# p128control.net
KiCad netlist of a schematic drawn in EAGLE
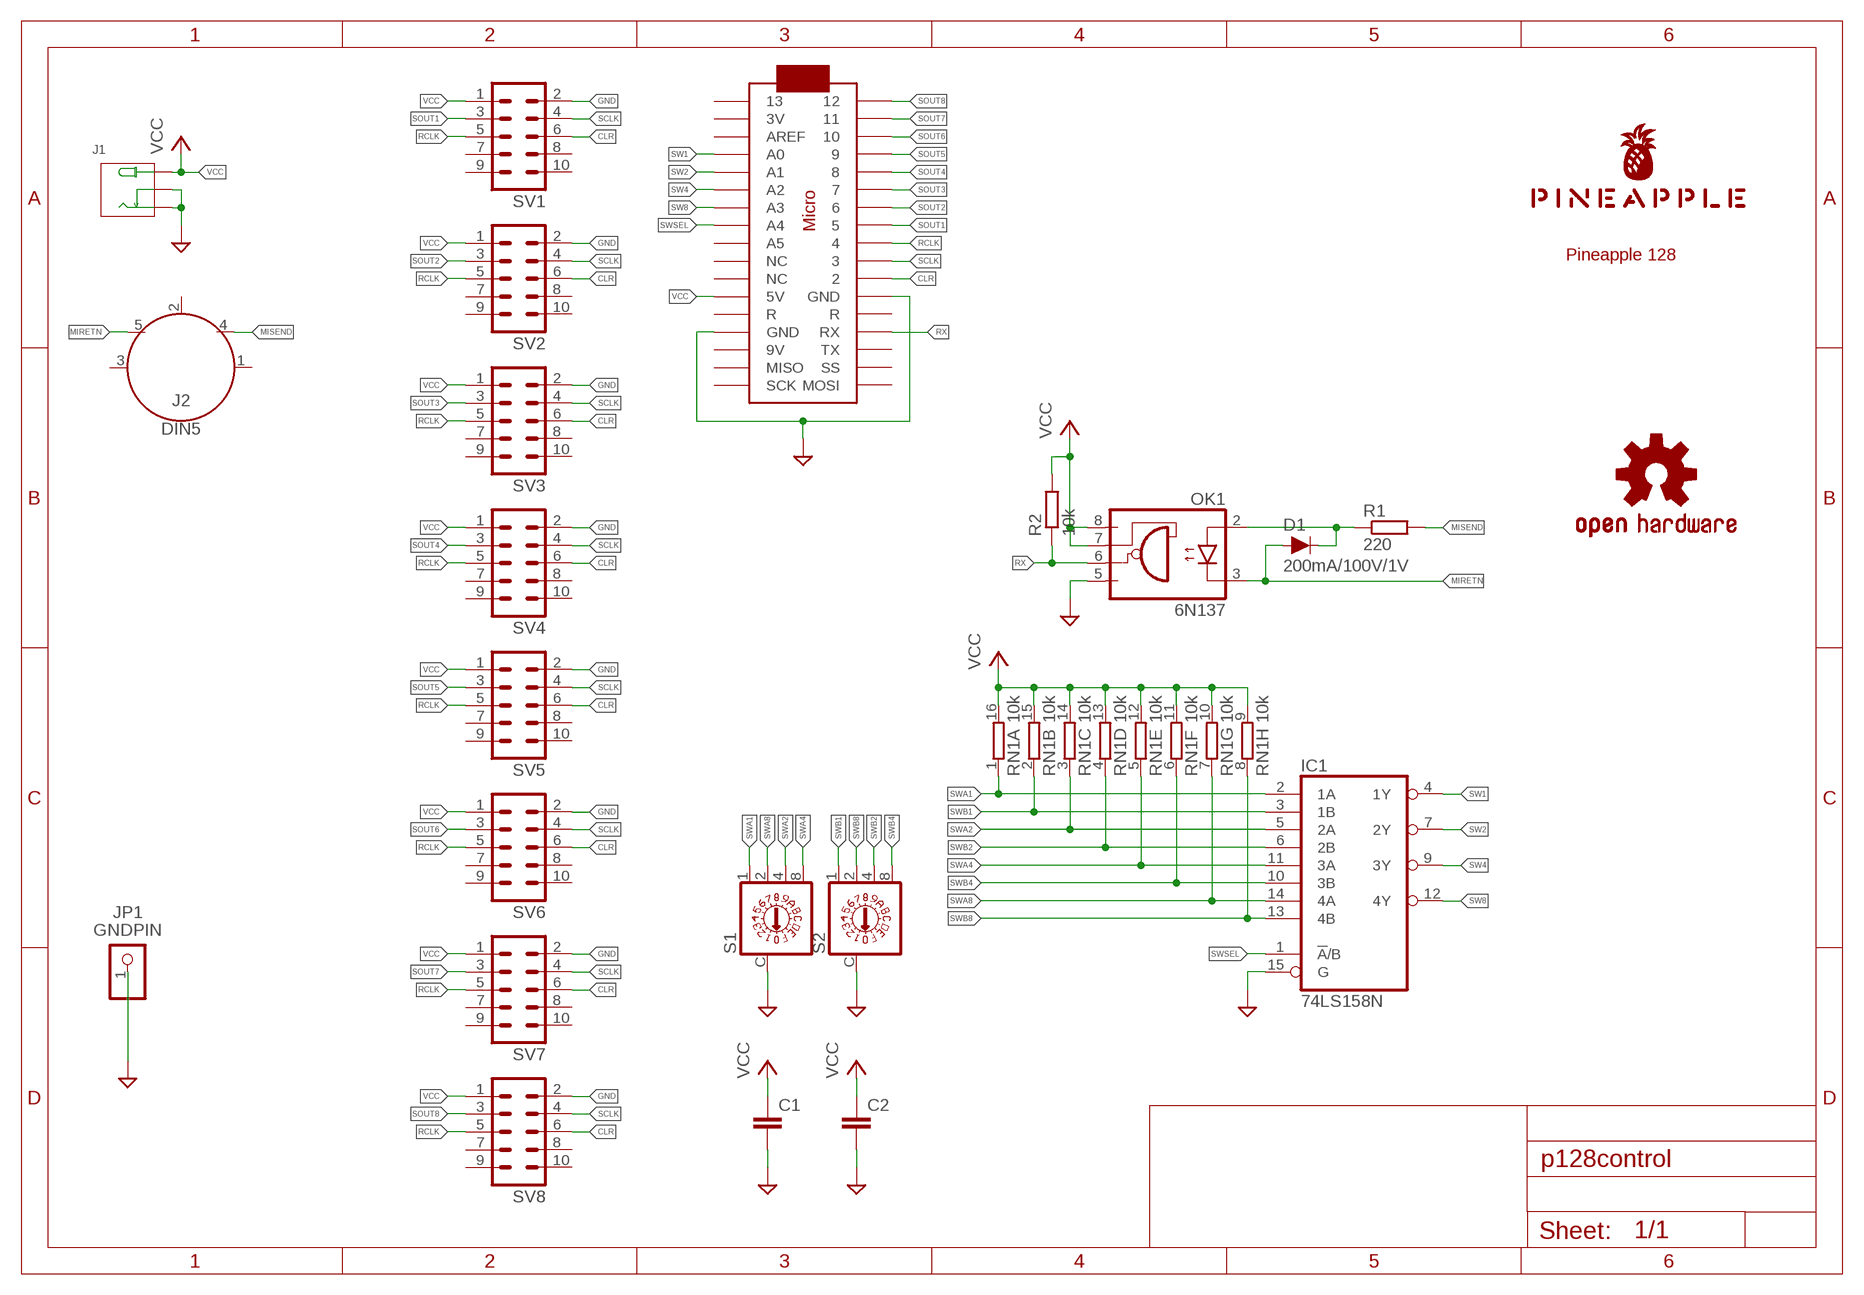
[diagram p0: schematic, sheet 1]

(export (version "E")
  (design (tool "Eeschema 10.0.6"))
  (components
    (comp (ref "C1")
      (value "C-EU025-024X044")
      (footprint "eagle-import:C025-024X044")
      (libsource (lib "eagle-import") (part "C-EU025-024X044"))
    )
    (comp (ref "C2")
      (value "C-EU025-024X044")
      (footprint "eagle-import:C025-024X044")
      (libsource (lib "eagle-import") (part "C-EU025-024X044"))
    )
    (comp (ref "D1")
      (value "200mA/100V/1V")
      (footprint "eagle-import:DIODE-1N4148")
      (libsource (lib "eagle-import") (part "DIODE-1N4148"))
    )
    (comp (ref "IC1")
      (value "74LS158N")
      (footprint "eagle-import:DIL16")
      (libsource (lib "eagle-import") (part "74158NLS"))
    )
    (comp (ref "J1")
      (value "JACK-DC-005'DC-005'")
      (footprint "eagle-import:3P-L14.2_W11.0_H9.0MM")
      (libsource (lib "eagle-import") (part "JACK-DC-005'DC-005'"))
    )
    (comp (ref "J2")
      (value "DIN5")
      (footprint "eagle-import:DIN5-RA-PTH")
      (libsource (lib "eagle-import") (part "DIN5"))
    )
    (comp (ref "JP1")
      (value "GNDPIN")
      (footprint "eagle-import:1X01")
      (libsource (lib "eagle-import") (part "PINHD-1X1"))
    )
    (comp (ref "LOGO1")
      (value "OSHW-LOGOS-COPPER")
      (footprint "eagle-import:OSHW-LOGO-S_COPPER")
      (libsource (lib "eagle-import") (part "OSHW-LOGOS-COPPER"))
    )
    (comp (ref "OK1")
      (value "6N137")
      (footprint "eagle-import:DIL08")
      (libsource (lib "eagle-import") (part "6N137"))
    )
    (comp (ref "R1")
      (value "220")
      (footprint "eagle-import:0204_5")
      (libsource (lib "eagle-import") (part "R-EU_0204/5"))
    )
    (comp (ref "R2")
      (value "10k")
      (footprint "eagle-import:0204_5")
      (libsource (lib "eagle-import") (part "R-EU_0204/5"))
    )
    (comp (ref "RN1")
      (value "10k")
      (footprint "eagle-import:DIL16")
      (libsource (lib "eagle-import") (part "8R-N"))
    )
    (comp (ref "S1")
      (value "A1353HEX")
      (footprint "eagle-import:A1353HEX")
      (libsource (lib "eagle-import") (part "A1353HEX"))
    )
    (comp (ref "S2")
      (value "A1353HEX")
      (footprint "eagle-import:A1353HEX")
      (libsource (lib "eagle-import") (part "A1353HEX"))
    )
    (comp (ref "SV1")
      (value "ML10")
      (footprint "eagle-import:ML10")
      (libsource (lib "eagle-import") (part "ML10"))
    )
    (comp (ref "SV2")
      (value "ML10")
      (footprint "eagle-import:ML10")
      (libsource (lib "eagle-import") (part "ML10"))
    )
    (comp (ref "SV3")
      (value "ML10")
      (footprint "eagle-import:ML10")
      (libsource (lib "eagle-import") (part "ML10"))
    )
    (comp (ref "SV4")
      (value "ML10")
      (footprint "eagle-import:ML10")
      (libsource (lib "eagle-import") (part "ML10"))
    )
    (comp (ref "SV5")
      (value "ML10")
      (footprint "eagle-import:ML10")
      (libsource (lib "eagle-import") (part "ML10"))
    )
    (comp (ref "SV6")
      (value "ML10")
      (footprint "eagle-import:ML10")
      (libsource (lib "eagle-import") (part "ML10"))
    )
    (comp (ref "SV7")
      (value "ML10")
      (footprint "eagle-import:ML10")
      (libsource (lib "eagle-import") (part "ML10"))
    )
    (comp (ref "SV8")
      (value "ML10")
      (footprint "eagle-import:ML10")
      (libsource (lib "eagle-import") (part "ML10"))
    )
    (comp (ref "U$1")
      (value "PINEAPPLE450_SILK")
      (footprint "eagle-import:PINEAPPLE450_SILK")
      (libsource (lib "eagle-import") (part "PINEAPPLE450_SILK"))
    )
    (comp (ref "U$2")
      (value "ARDUINOMICRO")
      (footprint "eagle-import:ARDUINOMICRO")
      (libsource (lib "eagle-import") (part "ARDUINOMICRO"))
    )
  )
  (nets
    (net (code "1") (name "CLR") (class "Default")
      (node (ref "SV1") (pin "6") (pinfunction "6_6") (pintype "passive"))
      (node (ref "SV2") (pin "6") (pinfunction "6_6") (pintype "passive"))
      (node (ref "SV3") (pin "6") (pinfunction "6_6") (pintype "passive"))
      (node (ref "SV4") (pin "6") (pinfunction "6_6") (pintype "passive"))
      (node (ref "SV5") (pin "6") (pinfunction "6_6") (pintype "passive"))
      (node (ref "SV6") (pin "6") (pinfunction "6_6") (pintype "passive"))
      (node (ref "SV7") (pin "6") (pinfunction "6_6") (pintype "passive"))
      (node (ref "SV8") (pin "6") (pinfunction "6_6") (pintype "passive"))
      (node (ref "U$2") (pin "P$11") (pinfunction "2_P$11") (pintype "bidirectional"))
    )
    (net (code "2") (name "GND") (class "Default")
      (node (ref "C1") (pin "2") (pinfunction "2_2") (pintype "passive"))
      (node (ref "C2") (pin "2") (pinfunction "2_2") (pintype "passive"))
      (node (ref "IC1") (pin "15") (pinfunction "G_15") (pintype "input"))
      (node (ref "J1") (pin "-1") (pinfunction "-_-1") (pintype "bidirectional"))
      (node (ref "J1") (pin "-2") (pinfunction "CDN_-2") (pintype "bidirectional"))
      (node (ref "JP1") (pin "1") (pinfunction "1_1") (pintype "passive"))
      (node (ref "OK1") (pin "5") (pinfunction "GND_5") (pintype "passive"))
      (node (ref "S1") (pin "C") (pinfunction "C_C") (pintype "passive"))
      (node (ref "S2") (pin "C") (pinfunction "C_C") (pintype "passive"))
      (node (ref "SV1") (pin "2") (pinfunction "2_2") (pintype "passive"))
      (node (ref "SV2") (pin "2") (pinfunction "2_2") (pintype "passive"))
      (node (ref "SV3") (pin "2") (pinfunction "2_2") (pintype "passive"))
      (node (ref "SV4") (pin "2") (pinfunction "2_2") (pintype "passive"))
      (node (ref "SV5") (pin "2") (pinfunction "2_2") (pintype "passive"))
      (node (ref "SV6") (pin "2") (pinfunction "2_2") (pintype "passive"))
      (node (ref "SV7") (pin "2") (pinfunction "2_2") (pintype "passive"))
      (node (ref "SV8") (pin "2") (pinfunction "2_2") (pintype "passive"))
      (node (ref "U$2") (pin "P$12") (pinfunction "GND_P$12") (pintype "bidirectional"))
      (node (ref "U$2") (pin "P$21") (pinfunction "GND_P$21") (pintype "bidirectional"))
    )
    (net (code "3") (name "MIRETN") (class "Default")
      (node (ref "D1") (pin "A") (pinfunction "A_A") (pintype "passive"))
      (node (ref "J2") (pin "5") (pinfunction "5_5") (pintype "bidirectional"))
      (node (ref "OK1") (pin "3") (pinfunction "C_3") (pintype "passive"))
    )
    (net (code "4") (name "MISEND") (class "Default")
      (node (ref "J2") (pin "4") (pinfunction "4_4") (pintype "bidirectional"))
      (node (ref "R1") (pin "2") (pinfunction "2_2") (pintype "passive"))
    )
    (net (code "5") (name "Net-(OK1-A)") (class "Default")
      (node (ref "D1") (pin "C") (pinfunction "C_C") (pintype "passive"))
      (node (ref "OK1") (pin "2") (pinfunction "A_2") (pintype "passive"))
      (node (ref "R1") (pin "1") (pinfunction "1_1") (pintype "passive"))
    )
    (net (code "6") (name "RCLK") (class "Default")
      (node (ref "SV1") (pin "5") (pinfunction "5_5") (pintype "passive"))
      (node (ref "SV2") (pin "5") (pinfunction "5_5") (pintype "passive"))
      (node (ref "SV3") (pin "5") (pinfunction "5_5") (pintype "passive"))
      (node (ref "SV4") (pin "5") (pinfunction "5_5") (pintype "passive"))
      (node (ref "SV5") (pin "5") (pinfunction "5_5") (pintype "passive"))
      (node (ref "SV6") (pin "5") (pinfunction "5_5") (pintype "passive"))
      (node (ref "SV7") (pin "5") (pinfunction "5_5") (pintype "passive"))
      (node (ref "SV8") (pin "5") (pinfunction "5_5") (pintype "passive"))
      (node (ref "U$2") (pin "P$9") (pinfunction "4_P$9") (pintype "bidirectional"))
    )
    (net (code "7") (name "RX") (class "Default")
      (node (ref "OK1") (pin "6") (pinfunction "VO_6") (pintype "passive"))
      (node (ref "R2") (pin "1") (pinfunction "1_1") (pintype "passive"))
      (node (ref "U$2") (pin "P$14") (pinfunction "RX_P$14") (pintype "bidirectional"))
    )
    (net (code "8") (name "SCLK") (class "Default")
      (node (ref "SV1") (pin "4") (pinfunction "4_4") (pintype "passive"))
      (node (ref "SV2") (pin "4") (pinfunction "4_4") (pintype "passive"))
      (node (ref "SV3") (pin "4") (pinfunction "4_4") (pintype "passive"))
      (node (ref "SV4") (pin "4") (pinfunction "4_4") (pintype "passive"))
      (node (ref "SV5") (pin "4") (pinfunction "4_4") (pintype "passive"))
      (node (ref "SV6") (pin "4") (pinfunction "4_4") (pintype "passive"))
      (node (ref "SV7") (pin "4") (pinfunction "4_4") (pintype "passive"))
      (node (ref "SV8") (pin "4") (pinfunction "4_4") (pintype "passive"))
      (node (ref "U$2") (pin "P$10") (pinfunction "3_P$10") (pintype "bidirectional"))
    )
    (net (code "9") (name "SOUT1") (class "Default")
      (node (ref "SV1") (pin "3") (pinfunction "3_3") (pintype "passive"))
      (node (ref "U$2") (pin "P$8") (pinfunction "5_P$8") (pintype "bidirectional"))
    )
    (net (code "10") (name "SOUT2") (class "Default")
      (node (ref "SV2") (pin "3") (pinfunction "3_3") (pintype "passive"))
      (node (ref "U$2") (pin "P$7") (pinfunction "6_P$7") (pintype "bidirectional"))
    )
    (net (code "11") (name "SOUT3") (class "Default")
      (node (ref "SV3") (pin "3") (pinfunction "3_3") (pintype "passive"))
      (node (ref "U$2") (pin "P$6") (pinfunction "7_P$6") (pintype "bidirectional"))
    )
    (net (code "12") (name "SOUT4") (class "Default")
      (node (ref "SV4") (pin "3") (pinfunction "3_3") (pintype "passive"))
      (node (ref "U$2") (pin "P$5") (pinfunction "8_P$5") (pintype "bidirectional"))
    )
    (net (code "13") (name "SOUT5") (class "Default")
      (node (ref "SV5") (pin "3") (pinfunction "3_3") (pintype "passive"))
      (node (ref "U$2") (pin "P$4") (pinfunction "9_P$4") (pintype "bidirectional"))
    )
    (net (code "14") (name "SOUT6") (class "Default")
      (node (ref "SV6") (pin "3") (pinfunction "3_3") (pintype "passive"))
      (node (ref "U$2") (pin "P$3") (pinfunction "10_P$3") (pintype "bidirectional"))
    )
    (net (code "15") (name "SOUT7") (class "Default")
      (node (ref "SV7") (pin "3") (pinfunction "3_3") (pintype "passive"))
      (node (ref "U$2") (pin "P$2") (pinfunction "11_P$2") (pintype "bidirectional"))
    )
    (net (code "16") (name "SOUT8") (class "Default")
      (node (ref "SV8") (pin "3") (pinfunction "3_3") (pintype "passive"))
      (node (ref "U$2") (pin "P$1") (pinfunction "12_P$1") (pintype "bidirectional"))
    )
    (net (code "17") (name "SW1") (class "Default")
      (node (ref "IC1") (pin "4") (pinfunction "1Y_4") (pintype "output"))
      (node (ref "U$2") (pin "P$31") (pinfunction "A0_P$31") (pintype "bidirectional"))
    )
    (net (code "18") (name "SW2") (class "Default")
      (node (ref "IC1") (pin "7") (pinfunction "2Y_7") (pintype "output"))
      (node (ref "U$2") (pin "P$30") (pinfunction "A1_P$30") (pintype "bidirectional"))
    )
    (net (code "19") (name "SW4") (class "Default")
      (node (ref "IC1") (pin "9") (pinfunction "3Y_9") (pintype "output"))
      (node (ref "U$2") (pin "P$29") (pinfunction "A2_P$29") (pintype "bidirectional"))
    )
    (net (code "20") (name "SW8") (class "Default")
      (node (ref "IC1") (pin "12") (pinfunction "4Y_12") (pintype "output"))
      (node (ref "U$2") (pin "P$28") (pinfunction "A3_P$28") (pintype "bidirectional"))
    )
    (net (code "21") (name "SWA1") (class "Default")
      (node (ref "IC1") (pin "2") (pinfunction "1A_2") (pintype "input"))
      (node (ref "RN1") (pin "1") (pinfunction "1_1") (pintype "passive"))
      (node (ref "S1") (pin "1") (pinfunction "1_1") (pintype "passive"))
    )
    (net (code "22") (name "SWA2") (class "Default")
      (node (ref "IC1") (pin "5") (pinfunction "2A_5") (pintype "input"))
      (node (ref "RN1") (pin "3") (pinfunction "1_3") (pintype "passive"))
      (node (ref "S1") (pin "4") (pinfunction "4_4") (pintype "passive"))
    )
    (net (code "23") (name "SWA4") (class "Default")
      (node (ref "IC1") (pin "11") (pinfunction "3A_11") (pintype "input"))
      (node (ref "RN1") (pin "5") (pinfunction "1_5") (pintype "passive"))
      (node (ref "S1") (pin "8") (pinfunction "8_8") (pintype "passive"))
    )
    (net (code "24") (name "SWA8") (class "Default")
      (node (ref "IC1") (pin "14") (pinfunction "4A_14") (pintype "input"))
      (node (ref "RN1") (pin "7") (pinfunction "1_7") (pintype "passive"))
      (node (ref "S1") (pin "2") (pinfunction "2_2") (pintype "passive"))
    )
    (net (code "25") (name "SWB1") (class "Default")
      (node (ref "IC1") (pin "3") (pinfunction "1B_3") (pintype "input"))
      (node (ref "RN1") (pin "2") (pinfunction "1_2") (pintype "passive"))
      (node (ref "S2") (pin "1") (pinfunction "1_1") (pintype "passive"))
    )
    (net (code "26") (name "SWB2") (class "Default")
      (node (ref "IC1") (pin "6") (pinfunction "2B_6") (pintype "input"))
      (node (ref "RN1") (pin "4") (pinfunction "1_4") (pintype "passive"))
      (node (ref "S2") (pin "4") (pinfunction "4_4") (pintype "passive"))
    )
    (net (code "27") (name "SWB4") (class "Default")
      (node (ref "IC1") (pin "10") (pinfunction "3B_10") (pintype "input"))
      (node (ref "RN1") (pin "6") (pinfunction "1_6") (pintype "passive"))
      (node (ref "S2") (pin "8") (pinfunction "8_8") (pintype "passive"))
    )
    (net (code "28") (name "SWB8") (class "Default")
      (node (ref "IC1") (pin "13") (pinfunction "4B_13") (pintype "input"))
      (node (ref "RN1") (pin "8") (pinfunction "1_8") (pintype "passive"))
      (node (ref "S2") (pin "2") (pinfunction "2_2") (pintype "passive"))
    )
    (net (code "29") (name "SWSEL") (class "Default")
      (node (ref "IC1") (pin "1") (pinfunction "~{A}/B_1") (pintype "input"))
      (node (ref "U$2") (pin "P$27") (pinfunction "A4_P$27") (pintype "bidirectional"))
    )
    (net (code "30") (name "VCC") (class "Default")
      (node (ref "C1") (pin "1") (pinfunction "1_1") (pintype "passive"))
      (node (ref "C2") (pin "1") (pinfunction "1_1") (pintype "passive"))
      (node (ref "J1") (pin "+") (pinfunction "+_+") (pintype "bidirectional"))
      (node (ref "OK1") (pin "7") (pinfunction "VE_7") (pintype "passive"))
      (node (ref "OK1") (pin "8") (pinfunction "VCC_8") (pintype "passive"))
      (node (ref "R2") (pin "2") (pinfunction "2_2") (pintype "passive"))
      (node (ref "RN1") (pin "10") (pinfunction "2_10") (pintype "passive"))
      (node (ref "RN1") (pin "11") (pinfunction "2_11") (pintype "passive"))
      (node (ref "RN1") (pin "12") (pinfunction "2_12") (pintype "passive"))
      (node (ref "RN1") (pin "13") (pinfunction "2_13") (pintype "passive"))
      (node (ref "RN1") (pin "14") (pinfunction "2_14") (pintype "passive"))
      (node (ref "RN1") (pin "15") (pinfunction "2_15") (pintype "passive"))
      (node (ref "RN1") (pin "16") (pinfunction "2_16") (pintype "passive"))
      (node (ref "RN1") (pin "9") (pinfunction "2_9") (pintype "passive"))
      (node (ref "SV1") (pin "1") (pinfunction "1_1") (pintype "passive"))
      (node (ref "SV2") (pin "1") (pinfunction "1_1") (pintype "passive"))
      (node (ref "SV3") (pin "1") (pinfunction "1_1") (pintype "passive"))
      (node (ref "SV4") (pin "1") (pinfunction "1_1") (pintype "passive"))
      (node (ref "SV5") (pin "1") (pinfunction "1_1") (pintype "passive"))
      (node (ref "SV6") (pin "1") (pinfunction "1_1") (pintype "passive"))
      (node (ref "SV7") (pin "1") (pinfunction "1_1") (pintype "passive"))
      (node (ref "SV8") (pin "1") (pinfunction "1_1") (pintype "passive"))
      (node (ref "U$2") (pin "P$23") (pinfunction "5V_P$23") (pintype "bidirectional"))
    )
    (net (code "31") (name "unconnected-(J2-Pad1)") (class "Default")
      (node (ref "J2") (pin "1") (pinfunction "1_1") (pintype "bidirectional"))
    )
    (net (code "32") (name "unconnected-(J2-Pad2)") (class "Default")
      (node (ref "J2") (pin "2") (pinfunction "2_2") (pintype "bidirectional"))
    )
    (net (code "33") (name "unconnected-(J2-Pad3)") (class "Default")
      (node (ref "J2") (pin "3") (pinfunction "3_3") (pintype "bidirectional"))
    )
    (net (code "34") (name "unconnected-(SV1-Pad7)") (class "Default")
      (node (ref "SV1") (pin "7") (pinfunction "7_7") (pintype "passive"))
    )
    (net (code "35") (name "unconnected-(SV1-Pad8)") (class "Default")
      (node (ref "SV1") (pin "8") (pinfunction "8_8") (pintype "passive"))
    )
    (net (code "36") (name "unconnected-(SV1-Pad9)") (class "Default")
      (node (ref "SV1") (pin "9") (pinfunction "9_9") (pintype "passive"))
    )
    (net (code "37") (name "unconnected-(SV1-Pad10)") (class "Default")
      (node (ref "SV1") (pin "10") (pinfunction "10_10") (pintype "passive"))
    )
    (net (code "38") (name "unconnected-(SV2-Pad7)") (class "Default")
      (node (ref "SV2") (pin "7") (pinfunction "7_7") (pintype "passive"))
    )
    (net (code "39") (name "unconnected-(SV2-Pad8)") (class "Default")
      (node (ref "SV2") (pin "8") (pinfunction "8_8") (pintype "passive"))
    )
    (net (code "40") (name "unconnected-(SV2-Pad9)") (class "Default")
      (node (ref "SV2") (pin "9") (pinfunction "9_9") (pintype "passive"))
    )
    (net (code "41") (name "unconnected-(SV2-Pad10)") (class "Default")
      (node (ref "SV2") (pin "10") (pinfunction "10_10") (pintype "passive"))
    )
    (net (code "42") (name "unconnected-(SV3-Pad7)") (class "Default")
      (node (ref "SV3") (pin "7") (pinfunction "7_7") (pintype "passive"))
    )
    (net (code "43") (name "unconnected-(SV3-Pad8)") (class "Default")
      (node (ref "SV3") (pin "8") (pinfunction "8_8") (pintype "passive"))
    )
    (net (code "44") (name "unconnected-(SV3-Pad9)") (class "Default")
      (node (ref "SV3") (pin "9") (pinfunction "9_9") (pintype "passive"))
    )
    (net (code "45") (name "unconnected-(SV3-Pad10)") (class "Default")
      (node (ref "SV3") (pin "10") (pinfunction "10_10") (pintype "passive"))
    )
    (net (code "46") (name "unconnected-(SV4-Pad7)") (class "Default")
      (node (ref "SV4") (pin "7") (pinfunction "7_7") (pintype "passive"))
    )
    (net (code "47") (name "unconnected-(SV4-Pad8)") (class "Default")
      (node (ref "SV4") (pin "8") (pinfunction "8_8") (pintype "passive"))
    )
    (net (code "48") (name "unconnected-(SV4-Pad9)") (class "Default")
      (node (ref "SV4") (pin "9") (pinfunction "9_9") (pintype "passive"))
    )
    (net (code "49") (name "unconnected-(SV4-Pad10)") (class "Default")
      (node (ref "SV4") (pin "10") (pinfunction "10_10") (pintype "passive"))
    )
    (net (code "50") (name "unconnected-(SV5-Pad7)") (class "Default")
      (node (ref "SV5") (pin "7") (pinfunction "7_7") (pintype "passive"))
    )
    (net (code "51") (name "unconnected-(SV5-Pad8)") (class "Default")
      (node (ref "SV5") (pin "8") (pinfunction "8_8") (pintype "passive"))
    )
    (net (code "52") (name "unconnected-(SV5-Pad9)") (class "Default")
      (node (ref "SV5") (pin "9") (pinfunction "9_9") (pintype "passive"))
    )
    (net (code "53") (name "unconnected-(SV5-Pad10)") (class "Default")
      (node (ref "SV5") (pin "10") (pinfunction "10_10") (pintype "passive"))
    )
    (net (code "54") (name "unconnected-(SV6-Pad7)") (class "Default")
      (node (ref "SV6") (pin "7") (pinfunction "7_7") (pintype "passive"))
    )
    (net (code "55") (name "unconnected-(SV6-Pad8)") (class "Default")
      (node (ref "SV6") (pin "8") (pinfunction "8_8") (pintype "passive"))
    )
    (net (code "56") (name "unconnected-(SV6-Pad9)") (class "Default")
      (node (ref "SV6") (pin "9") (pinfunction "9_9") (pintype "passive"))
    )
    (net (code "57") (name "unconnected-(SV6-Pad10)") (class "Default")
      (node (ref "SV6") (pin "10") (pinfunction "10_10") (pintype "passive"))
    )
    (net (code "58") (name "unconnected-(SV7-Pad7)") (class "Default")
      (node (ref "SV7") (pin "7") (pinfunction "7_7") (pintype "passive"))
    )
    (net (code "59") (name "unconnected-(SV7-Pad8)") (class "Default")
      (node (ref "SV7") (pin "8") (pinfunction "8_8") (pintype "passive"))
    )
    (net (code "60") (name "unconnected-(SV7-Pad9)") (class "Default")
      (node (ref "SV7") (pin "9") (pinfunction "9_9") (pintype "passive"))
    )
    (net (code "61") (name "unconnected-(SV7-Pad10)") (class "Default")
      (node (ref "SV7") (pin "10") (pinfunction "10_10") (pintype "passive"))
    )
    (net (code "62") (name "unconnected-(SV8-Pad7)") (class "Default")
      (node (ref "SV8") (pin "7") (pinfunction "7_7") (pintype "passive"))
    )
    (net (code "63") (name "unconnected-(SV8-Pad8)") (class "Default")
      (node (ref "SV8") (pin "8") (pinfunction "8_8") (pintype "passive"))
    )
    (net (code "64") (name "unconnected-(SV8-Pad9)") (class "Default")
      (node (ref "SV8") (pin "9") (pinfunction "9_9") (pintype "passive"))
    )
    (net (code "65") (name "unconnected-(SV8-Pad10)") (class "Default")
      (node (ref "SV8") (pin "10") (pinfunction "10_10") (pintype "passive"))
    )
    (net (code "66") (name "unconnected-(U$2-3V-PadP$33)") (class "Default")
      (node (ref "U$2") (pin "P$33") (pinfunction "3V_P$33") (pintype "bidirectional"))
    )
    (net (code "67") (name "unconnected-(U$2-9V-PadP$20)") (class "Default")
      (node (ref "U$2") (pin "P$20") (pinfunction "9V_P$20") (pintype "bidirectional"))
    )
    (net (code "68") (name "unconnected-(U$2-13-PadP$34)") (class "Default")
      (node (ref "U$2") (pin "P$34") (pinfunction "13_P$34") (pintype "bidirectional"))
    )
    (net (code "69") (name "unconnected-(U$2-A5-PadP$26)") (class "Default")
      (node (ref "U$2") (pin "P$26") (pinfunction "A5_P$26") (pintype "bidirectional"))
    )
    (net (code "70") (name "unconnected-(U$2-AREF-PadP$32)") (class "Default")
      (node (ref "U$2") (pin "P$32") (pinfunction "AREF_P$32") (pintype "bidirectional"))
    )
    (net (code "71") (name "unconnected-(U$2-MISO-PadP$19)") (class "Default")
      (node (ref "U$2") (pin "P$19") (pinfunction "MISO_P$19") (pintype "bidirectional"))
    )
    (net (code "72") (name "unconnected-(U$2-MOSI-PadP$17)") (class "Default")
      (node (ref "U$2") (pin "P$17") (pinfunction "MOSI_P$17") (pintype "bidirectional"))
    )
    (net (code "73") (name "unconnected-(U$2-NC-PadP$24)") (class "Default")
      (node (ref "U$2") (pin "P$24") (pinfunction "NC_P$24") (pintype "bidirectional"))
    )
    (net (code "74") (name "unconnected-(U$2-NC-PadP$25)") (class "Default")
      (node (ref "U$2") (pin "P$25") (pinfunction "NC_P$25") (pintype "bidirectional"))
    )
    (net (code "75") (name "unconnected-(U$2-R-PadP$13)") (class "Default")
      (node (ref "U$2") (pin "P$13") (pinfunction "R_P$13") (pintype "bidirectional"))
    )
    (net (code "76") (name "unconnected-(U$2-R-PadP$22)") (class "Default")
      (node (ref "U$2") (pin "P$22") (pinfunction "R_P$22") (pintype "bidirectional"))
    )
    (net (code "77") (name "unconnected-(U$2-SCK-PadP$18)") (class "Default")
      (node (ref "U$2") (pin "P$18") (pinfunction "SCK_P$18") (pintype "bidirectional"))
    )
    (net (code "78") (name "unconnected-(U$2-SS-PadP$16)") (class "Default")
      (node (ref "U$2") (pin "P$16") (pinfunction "SS_P$16") (pintype "bidirectional"))
    )
    (net (code "79") (name "unconnected-(U$2-TX-PadP$15)") (class "Default")
      (node (ref "U$2") (pin "P$15") (pinfunction "TX_P$15") (pintype "bidirectional"))
    )
  )
)
